# tablespoon.net
KiCad netlist of a schematic drawn in EAGLE
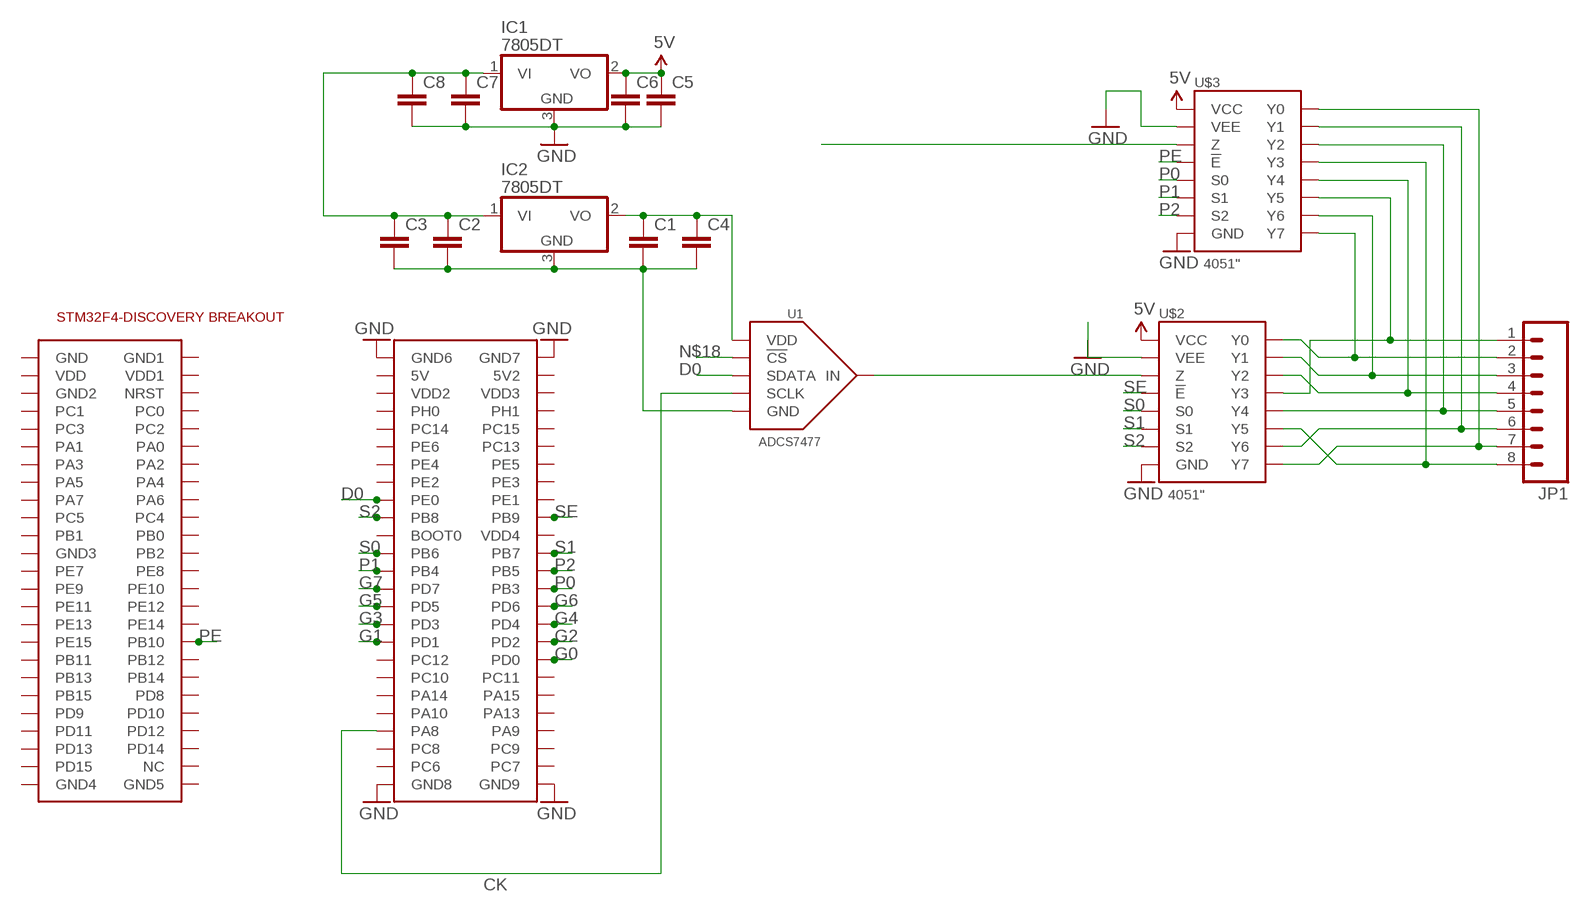
[diagram p0: schematic, sheet 1]

(export (version "E")
  (design (tool "Eeschema 10.0.6"))
  (components
    (comp (ref "C1")
      (value "C-EUC0805")
      (footprint "eagle-import:C0805")
      (libsource (lib "eagle-import") (part "C-EUC0805"))
    )
    (comp (ref "C2")
      (value "C-EUC0805")
      (footprint "eagle-import:C0805")
      (libsource (lib "eagle-import") (part "C-EUC0805"))
    )
    (comp (ref "C3")
      (value "C-EUC0805")
      (footprint "eagle-import:C0805")
      (libsource (lib "eagle-import") (part "C-EUC0805"))
    )
    (comp (ref "C4")
      (value "C-EUC0805")
      (footprint "eagle-import:C0805")
      (libsource (lib "eagle-import") (part "C-EUC0805"))
    )
    (comp (ref "C5")
      (value "C-EUC0805")
      (footprint "eagle-import:C0805")
      (libsource (lib "eagle-import") (part "C-EUC0805"))
    )
    (comp (ref "C6")
      (value "C-EUC0805")
      (footprint "eagle-import:C0805")
      (libsource (lib "eagle-import") (part "C-EUC0805"))
    )
    (comp (ref "C7")
      (value "C-EUC0805")
      (footprint "eagle-import:C0805")
      (libsource (lib "eagle-import") (part "C-EUC0805"))
    )
    (comp (ref "C8")
      (value "C-EUC0805")
      (footprint "eagle-import:C0805")
      (libsource (lib "eagle-import") (part "C-EUC0805"))
    )
    (comp (ref "IC1")
      (value "7805DT")
      (footprint "eagle-import:TO252")
      (libsource (lib "eagle-import") (part "78DT05"))
    )
    (comp (ref "IC2")
      (value "7805DT")
      (footprint "eagle-import:TO252")
      (libsource (lib "eagle-import") (part "78DT05"))
    )
    (comp (ref "JP1")
      (value "M08LONGPADS")
      (footprint "eagle-import:1X08_LONGPADS")
      (libsource (lib "eagle-import") (part "M08LONGPADS"))
    )
    (comp (ref "U$1")
      (value "STM32F4-DISCOVERY")
      (footprint "eagle-import:STM32F4-DISCOVERY")
      (libsource (lib "eagle-import") (part "STM32F4-DISCOVERY"))
    )
    (comp (ref "U$2")
      (value "4051\"")
      (footprint "eagle-import:TSSOP-16")
      (libsource (lib "eagle-import") (part "4051{dblquote}"))
    )
    (comp (ref "U$3")
      (value "4051\"")
      (footprint "eagle-import:TSSOP-16")
      (libsource (lib "eagle-import") (part "4051{dblquote}"))
    )
    (comp (ref "U1")
      (value "ADCS7477")
      (footprint "eagle-import:SOT-23-6")
      (libsource (lib "eagle-import") (part "ADCS7477"))
    )
  )
  (nets
    (net (code "1") (name "/CK") (class "Default")
      (node (ref "U$1") (pin "P$93") (pinfunction "PA8_P$93") (pintype "bidirectional"))
      (node (ref "U1") (pin "P$4") (pinfunction "SCLK_P$4") (pintype "bidirectional"))
    )
    (net (code "2") (name "/D0") (class "Default")
      (node (ref "U$1") (pin "P$67") (pinfunction "PE0_P$67") (pintype "bidirectional"))
      (node (ref "U1") (pin "P$5") (pinfunction "SDATA_P$5") (pintype "bidirectional"))
    )
    (net (code "3") (name "/G0") (class "Default")
      (node (ref "U$1") (pin "P$86") (pinfunction "PD0_P$86") (pintype "bidirectional"))
    )
    (net (code "4") (name "/G1") (class "Default")
      (node (ref "U$1") (pin "P$83") (pinfunction "PD1_P$83") (pintype "bidirectional"))
    )
    (net (code "5") (name "/G2") (class "Default")
      (node (ref "U$1") (pin "P$84") (pinfunction "PD2_P$84") (pintype "bidirectional"))
    )
    (net (code "6") (name "/G3") (class "Default")
      (node (ref "U$1") (pin "P$81") (pinfunction "PD3_P$81") (pintype "bidirectional"))
    )
    (net (code "7") (name "/G4") (class "Default")
      (node (ref "U$1") (pin "P$82") (pinfunction "PD4_P$82") (pintype "bidirectional"))
    )
    (net (code "8") (name "/G5") (class "Default")
      (node (ref "U$1") (pin "P$79") (pinfunction "PD5_P$79") (pintype "bidirectional"))
    )
    (net (code "9") (name "/G6") (class "Default")
      (node (ref "U$1") (pin "P$80") (pinfunction "PD6_P$80") (pintype "bidirectional"))
    )
    (net (code "10") (name "/G7") (class "Default")
      (node (ref "U$1") (pin "P$77") (pinfunction "PD7_P$77") (pintype "bidirectional"))
    )
    (net (code "11") (name "/N$18") (class "Default")
      (node (ref "U1") (pin "P$6") (pinfunction "~{CS}_P$6") (pintype "bidirectional"))
    )
    (net (code "12") (name "/P0") (class "Default")
      (node (ref "U$1") (pin "P$78") (pinfunction "PB3_P$78") (pintype "bidirectional"))
      (node (ref "U$3") (pin "P$11") (pinfunction "S0_P$11") (pintype "bidirectional"))
    )
    (net (code "13") (name "/P1") (class "Default")
      (node (ref "U$1") (pin "P$75") (pinfunction "PB4_P$75") (pintype "bidirectional"))
      (node (ref "U$3") (pin "P$10") (pinfunction "S1_P$10") (pintype "bidirectional"))
    )
    (net (code "14") (name "/P2") (class "Default")
      (node (ref "U$1") (pin "P$76") (pinfunction "PB5_P$76") (pintype "bidirectional"))
      (node (ref "U$3") (pin "P$9") (pinfunction "S2_P$9") (pintype "bidirectional"))
    )
    (net (code "15") (name "/PE") (class "Default")
      (node (ref "U$1") (pin "P$34") (pinfunction "PB10_P$34") (pintype "bidirectional"))
      (node (ref "U$3") (pin "P$6") (pinfunction "~{E}_P$6") (pintype "bidirectional"))
    )
    (net (code "16") (name "/S0") (class "Default")
      (node (ref "U$1") (pin "P$73") (pinfunction "PB6_P$73") (pintype "bidirectional"))
      (node (ref "U$2") (pin "P$11") (pinfunction "S0_P$11") (pintype "bidirectional"))
    )
    (net (code "17") (name "/S1") (class "Default")
      (node (ref "U$1") (pin "P$74") (pinfunction "PB7_P$74") (pintype "bidirectional"))
      (node (ref "U$2") (pin "P$10") (pinfunction "S1_P$10") (pintype "bidirectional"))
    )
    (net (code "18") (name "/S2") (class "Default")
      (node (ref "U$1") (pin "P$69") (pinfunction "PB8_P$69") (pintype "bidirectional"))
      (node (ref "U$2") (pin "P$9") (pinfunction "S2_P$9") (pintype "bidirectional"))
    )
    (net (code "19") (name "/SE") (class "Default")
      (node (ref "U$1") (pin "P$70") (pinfunction "PB9_P$70") (pintype "bidirectional"))
      (node (ref "U$2") (pin "P$6") (pinfunction "~{E}_P$6") (pintype "bidirectional"))
    )
    (net (code "20") (name "5V") (class "Default")
      (node (ref "C5") (pin "1") (pinfunction "1_1") (pintype "passive"))
      (node (ref "C6") (pin "1") (pinfunction "1_1") (pintype "passive"))
      (node (ref "IC1") (pin "2") (pinfunction "VO_2") (pintype "passive"))
      (node (ref "U$2") (pin "P$16") (pinfunction "VCC_P$16") (pintype "bidirectional"))
      (node (ref "U$3") (pin "P$16") (pinfunction "VCC_P$16") (pintype "bidirectional"))
    )
    (net (code "21") (name "GND") (class "Default")
      (node (ref "C5") (pin "2") (pinfunction "2_2") (pintype "passive"))
      (node (ref "C6") (pin "2") (pinfunction "2_2") (pintype "passive"))
      (node (ref "C7") (pin "2") (pinfunction "2_2") (pintype "passive"))
      (node (ref "C8") (pin "2") (pinfunction "2_2") (pintype "passive"))
      (node (ref "IC1") (pin "3") (pinfunction "GND_3") (pintype "passive"))
      (node (ref "U$1") (pin "P$100") (pinfunction "GND9_P$100") (pintype "bidirectional"))
      (node (ref "U$1") (pin "P$51") (pinfunction "GND6_P$51") (pintype "bidirectional"))
      (node (ref "U$1") (pin "P$52") (pinfunction "GND7_P$52") (pintype "bidirectional"))
      (node (ref "U$1") (pin "P$99") (pinfunction "GND8_P$99") (pintype "bidirectional"))
      (node (ref "U$2") (pin "P$7") (pinfunction "VEE_P$7") (pintype "bidirectional"))
      (node (ref "U$2") (pin "P$8") (pinfunction "GND_P$8") (pintype "bidirectional"))
      (node (ref "U$3") (pin "P$7") (pinfunction "VEE_P$7") (pintype "bidirectional"))
      (node (ref "U$3") (pin "P$8") (pinfunction "GND_P$8") (pintype "bidirectional"))
    )
    (net (code "22") (name "Net-(IC1-VI)") (class "Default")
      (node (ref "C2") (pin "1") (pinfunction "1_1") (pintype "passive"))
      (node (ref "C3") (pin "1") (pinfunction "1_1") (pintype "passive"))
      (node (ref "C7") (pin "1") (pinfunction "1_1") (pintype "passive"))
      (node (ref "C8") (pin "1") (pinfunction "1_1") (pintype "passive"))
      (node (ref "IC1") (pin "1") (pinfunction "VI_1") (pintype "input"))
      (node (ref "IC2") (pin "1") (pinfunction "VI_1") (pintype "input"))
    )
    (net (code "23") (name "Net-(IC2-GND)") (class "Default")
      (node (ref "C1") (pin "2") (pinfunction "2_2") (pintype "passive"))
      (node (ref "C2") (pin "2") (pinfunction "2_2") (pintype "passive"))
      (node (ref "C3") (pin "2") (pinfunction "2_2") (pintype "passive"))
      (node (ref "C4") (pin "2") (pinfunction "2_2") (pintype "passive"))
      (node (ref "IC2") (pin "3") (pinfunction "GND_3") (pintype "passive"))
      (node (ref "U1") (pin "P$2") (pinfunction "GND_P$2") (pintype "bidirectional"))
    )
    (net (code "24") (name "Net-(IC2-VO)") (class "Default")
      (node (ref "C1") (pin "1") (pinfunction "1_1") (pintype "passive"))
      (node (ref "C4") (pin "1") (pinfunction "1_1") (pintype "passive"))
      (node (ref "IC2") (pin "2") (pinfunction "VO_2") (pintype "passive"))
      (node (ref "U1") (pin "P$1") (pinfunction "VDD_P$1") (pintype "bidirectional"))
    )
    (net (code "25") (name "Net-(U$2-Y0)") (class "Default")
      (node (ref "JP1") (pin "2") (pinfunction "2_2") (pintype "passive"))
      (node (ref "U$2") (pin "P$13") (pinfunction "Y0_P$13") (pintype "bidirectional"))
      (node (ref "U$3") (pin "P$4") (pinfunction "Y7_P$4") (pintype "bidirectional"))
    )
    (net (code "26") (name "Net-(U$2-Y1)") (class "Default")
      (node (ref "JP1") (pin "3") (pinfunction "3_3") (pintype "passive"))
      (node (ref "U$2") (pin "P$14") (pinfunction "Y1_P$14") (pintype "bidirectional"))
      (node (ref "U$3") (pin "P$2") (pinfunction "Y6_P$2") (pintype "bidirectional"))
    )
    (net (code "27") (name "Net-(U$2-Y2)") (class "Default")
      (node (ref "JP1") (pin "4") (pinfunction "4_4") (pintype "passive"))
      (node (ref "U$2") (pin "P$15") (pinfunction "Y2_P$15") (pintype "bidirectional"))
      (node (ref "U$3") (pin "P$1") (pinfunction "Y4_P$1") (pintype "bidirectional"))
    )
    (net (code "28") (name "Net-(U$2-Y3)") (class "Default")
      (node (ref "JP1") (pin "1") (pinfunction "1_1") (pintype "passive"))
      (node (ref "U$2") (pin "P$12") (pinfunction "Y3_P$12") (pintype "bidirectional"))
      (node (ref "U$3") (pin "P$5") (pinfunction "Y5_P$5") (pintype "bidirectional"))
    )
    (net (code "29") (name "Net-(U$2-Y4)") (class "Default")
      (node (ref "JP1") (pin "5") (pinfunction "5_5") (pintype "passive"))
      (node (ref "U$2") (pin "P$1") (pinfunction "Y4_P$1") (pintype "bidirectional"))
      (node (ref "U$3") (pin "P$15") (pinfunction "Y2_P$15") (pintype "bidirectional"))
    )
    (net (code "30") (name "Net-(U$2-Y5)") (class "Default")
      (node (ref "JP1") (pin "8") (pinfunction "8_8") (pintype "passive"))
      (node (ref "U$2") (pin "P$5") (pinfunction "Y5_P$5") (pintype "bidirectional"))
      (node (ref "U$3") (pin "P$12") (pinfunction "Y3_P$12") (pintype "bidirectional"))
    )
    (net (code "31") (name "Net-(U$2-Y6)") (class "Default")
      (node (ref "JP1") (pin "6") (pinfunction "6_6") (pintype "passive"))
      (node (ref "U$2") (pin "P$2") (pinfunction "Y6_P$2") (pintype "bidirectional"))
      (node (ref "U$3") (pin "P$14") (pinfunction "Y1_P$14") (pintype "bidirectional"))
    )
    (net (code "32") (name "Net-(U$2-Y7)") (class "Default")
      (node (ref "JP1") (pin "7") (pinfunction "7_7") (pintype "passive"))
      (node (ref "U$2") (pin "P$4") (pinfunction "Y7_P$4") (pintype "bidirectional"))
      (node (ref "U$3") (pin "P$13") (pinfunction "Y0_P$13") (pintype "bidirectional"))
    )
    (net (code "33") (name "Net-(U$2-Z)") (class "Default")
      (node (ref "U$2") (pin "P$3") (pinfunction "Z_P$3") (pintype "bidirectional"))
      (node (ref "U1") (pin "P$3") (pinfunction "IN_P$3") (pintype "bidirectional"))
    )
    (net (code "34") (name "unconnected-(U$1-5V-PadP$53)") (class "Default")
      (node (ref "U$1") (pin "P$53") (pinfunction "5V_P$53") (pintype "bidirectional"))
    )
    (net (code "35") (name "unconnected-(U$1-5V2-PadP$54)") (class "Default")
      (node (ref "U$1") (pin "P$54") (pinfunction "5V2_P$54") (pintype "bidirectional"))
    )
    (net (code "36") (name "unconnected-(U$1-BOOT0-PadP$71)") (class "Default")
      (node (ref "U$1") (pin "P$71") (pinfunction "BOOT0_P$71") (pintype "bidirectional"))
    )
    (net (code "37") (name "unconnected-(U$1-GND-PadP$1)") (class "Default")
      (node (ref "U$1") (pin "P$1") (pinfunction "GND_P$1") (pintype "bidirectional"))
    )
    (net (code "38") (name "unconnected-(U$1-GND1-PadP$2)") (class "Default")
      (node (ref "U$1") (pin "P$2") (pinfunction "GND1_P$2") (pintype "bidirectional"))
    )
    (net (code "39") (name "unconnected-(U$1-GND2-PadP$5)") (class "Default")
      (node (ref "U$1") (pin "P$5") (pinfunction "GND2_P$5") (pintype "bidirectional"))
    )
    (net (code "40") (name "unconnected-(U$1-GND3-PadP$23)") (class "Default")
      (node (ref "U$1") (pin "P$23") (pinfunction "GND3_P$23") (pintype "bidirectional"))
    )
    (net (code "41") (name "unconnected-(U$1-GND4-PadP$49)") (class "Default")
      (node (ref "U$1") (pin "P$49") (pinfunction "GND4_P$49") (pintype "bidirectional"))
    )
    (net (code "42") (name "unconnected-(U$1-GND5-PadP$50)") (class "Default")
      (node (ref "U$1") (pin "P$50") (pinfunction "GND5_P$50") (pintype "bidirectional"))
    )
    (net (code "43") (name "unconnected-(U$1-NC-PadP$48)") (class "Default")
      (node (ref "U$1") (pin "P$48") (pinfunction "NC_P$48") (pintype "bidirectional"))
    )
    (net (code "44") (name "unconnected-(U$1-NRST-PadP$6)") (class "Default")
      (node (ref "U$1") (pin "P$6") (pinfunction "NRST_P$6") (pintype "bidirectional"))
    )
    (net (code "45") (name "unconnected-(U$1-PA0-PadP$12)") (class "Default")
      (node (ref "U$1") (pin "P$12") (pinfunction "PA0_P$12") (pintype "bidirectional"))
    )
    (net (code "46") (name "unconnected-(U$1-PA1-PadP$11)") (class "Default")
      (node (ref "U$1") (pin "P$11") (pinfunction "PA1_P$11") (pintype "bidirectional"))
    )
    (net (code "47") (name "unconnected-(U$1-PA2-PadP$14)") (class "Default")
      (node (ref "U$1") (pin "P$14") (pinfunction "PA2_P$14") (pintype "bidirectional"))
    )
    (net (code "48") (name "unconnected-(U$1-PA3-PadP$13)") (class "Default")
      (node (ref "U$1") (pin "P$13") (pinfunction "PA3_P$13") (pintype "bidirectional"))
    )
    (net (code "49") (name "unconnected-(U$1-PA4-PadP$16)") (class "Default")
      (node (ref "U$1") (pin "P$16") (pinfunction "PA4_P$16") (pintype "bidirectional"))
    )
    (net (code "50") (name "unconnected-(U$1-PA5-PadP$15)") (class "Default")
      (node (ref "U$1") (pin "P$15") (pinfunction "PA5_P$15") (pintype "bidirectional"))
    )
    (net (code "51") (name "unconnected-(U$1-PA6-PadP$18)") (class "Default")
      (node (ref "U$1") (pin "P$18") (pinfunction "PA6_P$18") (pintype "bidirectional"))
    )
    (net (code "52") (name "unconnected-(U$1-PA7-PadP$17)") (class "Default")
      (node (ref "U$1") (pin "P$17") (pinfunction "PA7_P$17") (pintype "bidirectional"))
    )
    (net (code "53") (name "unconnected-(U$1-PA9-PadP$94)") (class "Default")
      (node (ref "U$1") (pin "P$94") (pinfunction "PA9_P$94") (pintype "bidirectional"))
    )
    (net (code "54") (name "unconnected-(U$1-PA10-PadP$91)") (class "Default")
      (node (ref "U$1") (pin "P$91") (pinfunction "PA10_P$91") (pintype "bidirectional"))
    )
    (net (code "55") (name "unconnected-(U$1-PA13-PadP$92)") (class "Default")
      (node (ref "U$1") (pin "P$92") (pinfunction "PA13_P$92") (pintype "bidirectional"))
    )
    (net (code "56") (name "unconnected-(U$1-PA14-PadP$89)") (class "Default")
      (node (ref "U$1") (pin "P$89") (pinfunction "PA14_P$89") (pintype "bidirectional"))
    )
    (net (code "57") (name "unconnected-(U$1-PA15-PadP$90)") (class "Default")
      (node (ref "U$1") (pin "P$90") (pinfunction "PA15_P$90") (pintype "bidirectional"))
    )
    (net (code "58") (name "unconnected-(U$1-PB0-PadP$22)") (class "Default")
      (node (ref "U$1") (pin "P$22") (pinfunction "PB0_P$22") (pintype "bidirectional"))
    )
    (net (code "59") (name "unconnected-(U$1-PB1-PadP$21)") (class "Default")
      (node (ref "U$1") (pin "P$21") (pinfunction "PB1_P$21") (pintype "bidirectional"))
    )
    (net (code "60") (name "unconnected-(U$1-PB2-PadP$24)") (class "Default")
      (node (ref "U$1") (pin "P$24") (pinfunction "PB2_P$24") (pintype "bidirectional"))
    )
    (net (code "61") (name "unconnected-(U$1-PB11-PadP$35)") (class "Default")
      (node (ref "U$1") (pin "P$35") (pinfunction "PB11_P$35") (pintype "bidirectional"))
    )
    (net (code "62") (name "unconnected-(U$1-PB12-PadP$36)") (class "Default")
      (node (ref "U$1") (pin "P$36") (pinfunction "PB12_P$36") (pintype "bidirectional"))
    )
    (net (code "63") (name "unconnected-(U$1-PB13-PadP$37)") (class "Default")
      (node (ref "U$1") (pin "P$37") (pinfunction "PB13_P$37") (pintype "bidirectional"))
    )
    (net (code "64") (name "unconnected-(U$1-PB14-PadP$38)") (class "Default")
      (node (ref "U$1") (pin "P$38") (pinfunction "PB14_P$38") (pintype "bidirectional"))
    )
    (net (code "65") (name "unconnected-(U$1-PB15-PadP$39)") (class "Default")
      (node (ref "U$1") (pin "P$39") (pinfunction "PB15_P$39") (pintype "bidirectional"))
    )
    (net (code "66") (name "unconnected-(U$1-PC0-PadP$8)") (class "Default")
      (node (ref "U$1") (pin "P$8") (pinfunction "PC0_P$8") (pintype "bidirectional"))
    )
    (net (code "67") (name "unconnected-(U$1-PC1-PadP$7)") (class "Default")
      (node (ref "U$1") (pin "P$7") (pinfunction "PC1_P$7") (pintype "bidirectional"))
    )
    (net (code "68") (name "unconnected-(U$1-PC2-PadP$10)") (class "Default")
      (node (ref "U$1") (pin "P$10") (pinfunction "PC2_P$10") (pintype "bidirectional"))
    )
    (net (code "69") (name "unconnected-(U$1-PC3-PadP$9)") (class "Default")
      (node (ref "U$1") (pin "P$9") (pinfunction "PC3_P$9") (pintype "bidirectional"))
    )
    (net (code "70") (name "unconnected-(U$1-PC4-PadP$20)") (class "Default")
      (node (ref "U$1") (pin "P$20") (pinfunction "PC4_P$20") (pintype "bidirectional"))
    )
    (net (code "71") (name "unconnected-(U$1-PC5-PadP$19)") (class "Default")
      (node (ref "U$1") (pin "P$19") (pinfunction "PC5_P$19") (pintype "bidirectional"))
    )
    (net (code "72") (name "unconnected-(U$1-PC6-PadP$97)") (class "Default")
      (node (ref "U$1") (pin "P$97") (pinfunction "PC6_P$97") (pintype "bidirectional"))
    )
    (net (code "73") (name "unconnected-(U$1-PC7-PadP$98)") (class "Default")
      (node (ref "U$1") (pin "P$98") (pinfunction "PC7_P$98") (pintype "bidirectional"))
    )
    (net (code "74") (name "unconnected-(U$1-PC8-PadP$95)") (class "Default")
      (node (ref "U$1") (pin "P$95") (pinfunction "PC8_P$95") (pintype "bidirectional"))
    )
    (net (code "75") (name "unconnected-(U$1-PC9-PadP$96)") (class "Default")
      (node (ref "U$1") (pin "P$96") (pinfunction "PC9_P$96") (pintype "bidirectional"))
    )
    (net (code "76") (name "unconnected-(U$1-PC10-PadP$87)") (class "Default")
      (node (ref "U$1") (pin "P$87") (pinfunction "PC10_P$87") (pintype "bidirectional"))
    )
    (net (code "77") (name "unconnected-(U$1-PC11-PadP$88)") (class "Default")
      (node (ref "U$1") (pin "P$88") (pinfunction "PC11_P$88") (pintype "bidirectional"))
    )
    (net (code "78") (name "unconnected-(U$1-PC12-PadP$85)") (class "Default")
      (node (ref "U$1") (pin "P$85") (pinfunction "PC12_P$85") (pintype "bidirectional"))
    )
    (net (code "79") (name "unconnected-(U$1-PC13-PadP$62)") (class "Default")
      (node (ref "U$1") (pin "P$62") (pinfunction "PC13_P$62") (pintype "bidirectional"))
    )
    (net (code "80") (name "unconnected-(U$1-PC14-PadP$59)") (class "Default")
      (node (ref "U$1") (pin "P$59") (pinfunction "PC14_P$59") (pintype "bidirectional"))
    )
    (net (code "81") (name "unconnected-(U$1-PC15-PadP$60)") (class "Default")
      (node (ref "U$1") (pin "P$60") (pinfunction "PC15_P$60") (pintype "bidirectional"))
    )
    (net (code "82") (name "unconnected-(U$1-PD8-PadP$40)") (class "Default")
      (node (ref "U$1") (pin "P$40") (pinfunction "PD8_P$40") (pintype "bidirectional"))
    )
    (net (code "83") (name "unconnected-(U$1-PD9-PadP$41)") (class "Default")
      (node (ref "U$1") (pin "P$41") (pinfunction "PD9_P$41") (pintype "bidirectional"))
    )
    (net (code "84") (name "unconnected-(U$1-PD10-PadP$42)") (class "Default")
      (node (ref "U$1") (pin "P$42") (pinfunction "PD10_P$42") (pintype "bidirectional"))
    )
    (net (code "85") (name "unconnected-(U$1-PD11-PadP$43)") (class "Default")
      (node (ref "U$1") (pin "P$43") (pinfunction "PD11_P$43") (pintype "bidirectional"))
    )
    (net (code "86") (name "unconnected-(U$1-PD12-PadP$44)") (class "Default")
      (node (ref "U$1") (pin "P$44") (pinfunction "PD12_P$44") (pintype "bidirectional"))
    )
    (net (code "87") (name "unconnected-(U$1-PD13-PadP$45)") (class "Default")
      (node (ref "U$1") (pin "P$45") (pinfunction "PD13_P$45") (pintype "bidirectional"))
    )
    (net (code "88") (name "unconnected-(U$1-PD14-PadP$46)") (class "Default")
      (node (ref "U$1") (pin "P$46") (pinfunction "PD14_P$46") (pintype "bidirectional"))
    )
    (net (code "89") (name "unconnected-(U$1-PD15-PadP$47)") (class "Default")
      (node (ref "U$1") (pin "P$47") (pinfunction "PD15_P$47") (pintype "bidirectional"))
    )
    (net (code "90") (name "unconnected-(U$1-PE1-PadP$68)") (class "Default")
      (node (ref "U$1") (pin "P$68") (pinfunction "PE1_P$68") (pintype "bidirectional"))
    )
    (net (code "91") (name "unconnected-(U$1-PE2-PadP$65)") (class "Default")
      (node (ref "U$1") (pin "P$65") (pinfunction "PE2_P$65") (pintype "bidirectional"))
    )
    (net (code "92") (name "unconnected-(U$1-PE3-PadP$66)") (class "Default")
      (node (ref "U$1") (pin "P$66") (pinfunction "PE3_P$66") (pintype "bidirectional"))
    )
    (net (code "93") (name "unconnected-(U$1-PE4-PadP$63)") (class "Default")
      (node (ref "U$1") (pin "P$63") (pinfunction "PE4_P$63") (pintype "bidirectional"))
    )
    (net (code "94") (name "unconnected-(U$1-PE5-PadP$64)") (class "Default")
      (node (ref "U$1") (pin "P$64") (pinfunction "PE5_P$64") (pintype "bidirectional"))
    )
    (net (code "95") (name "unconnected-(U$1-PE6-PadP$61)") (class "Default")
      (node (ref "U$1") (pin "P$61") (pinfunction "PE6_P$61") (pintype "bidirectional"))
    )
    (net (code "96") (name "unconnected-(U$1-PE7-PadP$25)") (class "Default")
      (node (ref "U$1") (pin "P$25") (pinfunction "PE7_P$25") (pintype "bidirectional"))
    )
    (net (code "97") (name "unconnected-(U$1-PE8-PadP$26)") (class "Default")
      (node (ref "U$1") (pin "P$26") (pinfunction "PE8_P$26") (pintype "bidirectional"))
    )
    (net (code "98") (name "unconnected-(U$1-PE9-PadP$27)") (class "Default")
      (node (ref "U$1") (pin "P$27") (pinfunction "PE9_P$27") (pintype "bidirectional"))
    )
    (net (code "99") (name "unconnected-(U$1-PE10-PadP$28)") (class "Default")
      (node (ref "U$1") (pin "P$28") (pinfunction "PE10_P$28") (pintype "bidirectional"))
    )
    (net (code "100") (name "unconnected-(U$1-PE11-PadP$29)") (class "Default")
      (node (ref "U$1") (pin "P$29") (pinfunction "PE11_P$29") (pintype "bidirectional"))
    )
    (net (code "101") (name "unconnected-(U$1-PE12-PadP$30)") (class "Default")
      (node (ref "U$1") (pin "P$30") (pinfunction "PE12_P$30") (pintype "bidirectional"))
    )
    (net (code "102") (name "unconnected-(U$1-PE13-PadP$31)") (class "Default")
      (node (ref "U$1") (pin "P$31") (pinfunction "PE13_P$31") (pintype "bidirectional"))
    )
    (net (code "103") (name "unconnected-(U$1-PE14-PadP$32)") (class "Default")
      (node (ref "U$1") (pin "P$32") (pinfunction "PE14_P$32") (pintype "bidirectional"))
    )
    (net (code "104") (name "unconnected-(U$1-PE15-PadP$33)") (class "Default")
      (node (ref "U$1") (pin "P$33") (pinfunction "PE15_P$33") (pintype "bidirectional"))
    )
    (net (code "105") (name "unconnected-(U$1-PH0-PadP$57)") (class "Default")
      (node (ref "U$1") (pin "P$57") (pinfunction "PH0_P$57") (pintype "bidirectional"))
    )
    (net (code "106") (name "unconnected-(U$1-PH1-PadP$58)") (class "Default")
      (node (ref "U$1") (pin "P$58") (pinfunction "PH1_P$58") (pintype "bidirectional"))
    )
    (net (code "107") (name "unconnected-(U$1-VDD-PadP$3)") (class "Default")
      (node (ref "U$1") (pin "P$3") (pinfunction "VDD_P$3") (pintype "bidirectional"))
    )
    (net (code "108") (name "unconnected-(U$1-VDD1-PadP$4)") (class "Default")
      (node (ref "U$1") (pin "P$4") (pinfunction "VDD1_P$4") (pintype "bidirectional"))
    )
    (net (code "109") (name "unconnected-(U$1-VDD2-PadP$55)") (class "Default")
      (node (ref "U$1") (pin "P$55") (pinfunction "VDD2_P$55") (pintype "bidirectional"))
    )
    (net (code "110") (name "unconnected-(U$1-VDD3-PadP$56)") (class "Default")
      (node (ref "U$1") (pin "P$56") (pinfunction "VDD3_P$56") (pintype "bidirectional"))
    )
    (net (code "111") (name "unconnected-(U$1-VDD4-PadP$72)") (class "Default")
      (node (ref "U$1") (pin "P$72") (pinfunction "VDD4_P$72") (pintype "bidirectional"))
    )
    (net (code "112") (name "unconnected-(U$3-Z-PadP$3)") (class "Default")
      (node (ref "U$3") (pin "P$3") (pinfunction "Z_P$3") (pintype "bidirectional"))
    )
  )
)
